# YutaAndJialiang_v17.net
KiCad netlist of a schematic drawn in EAGLE
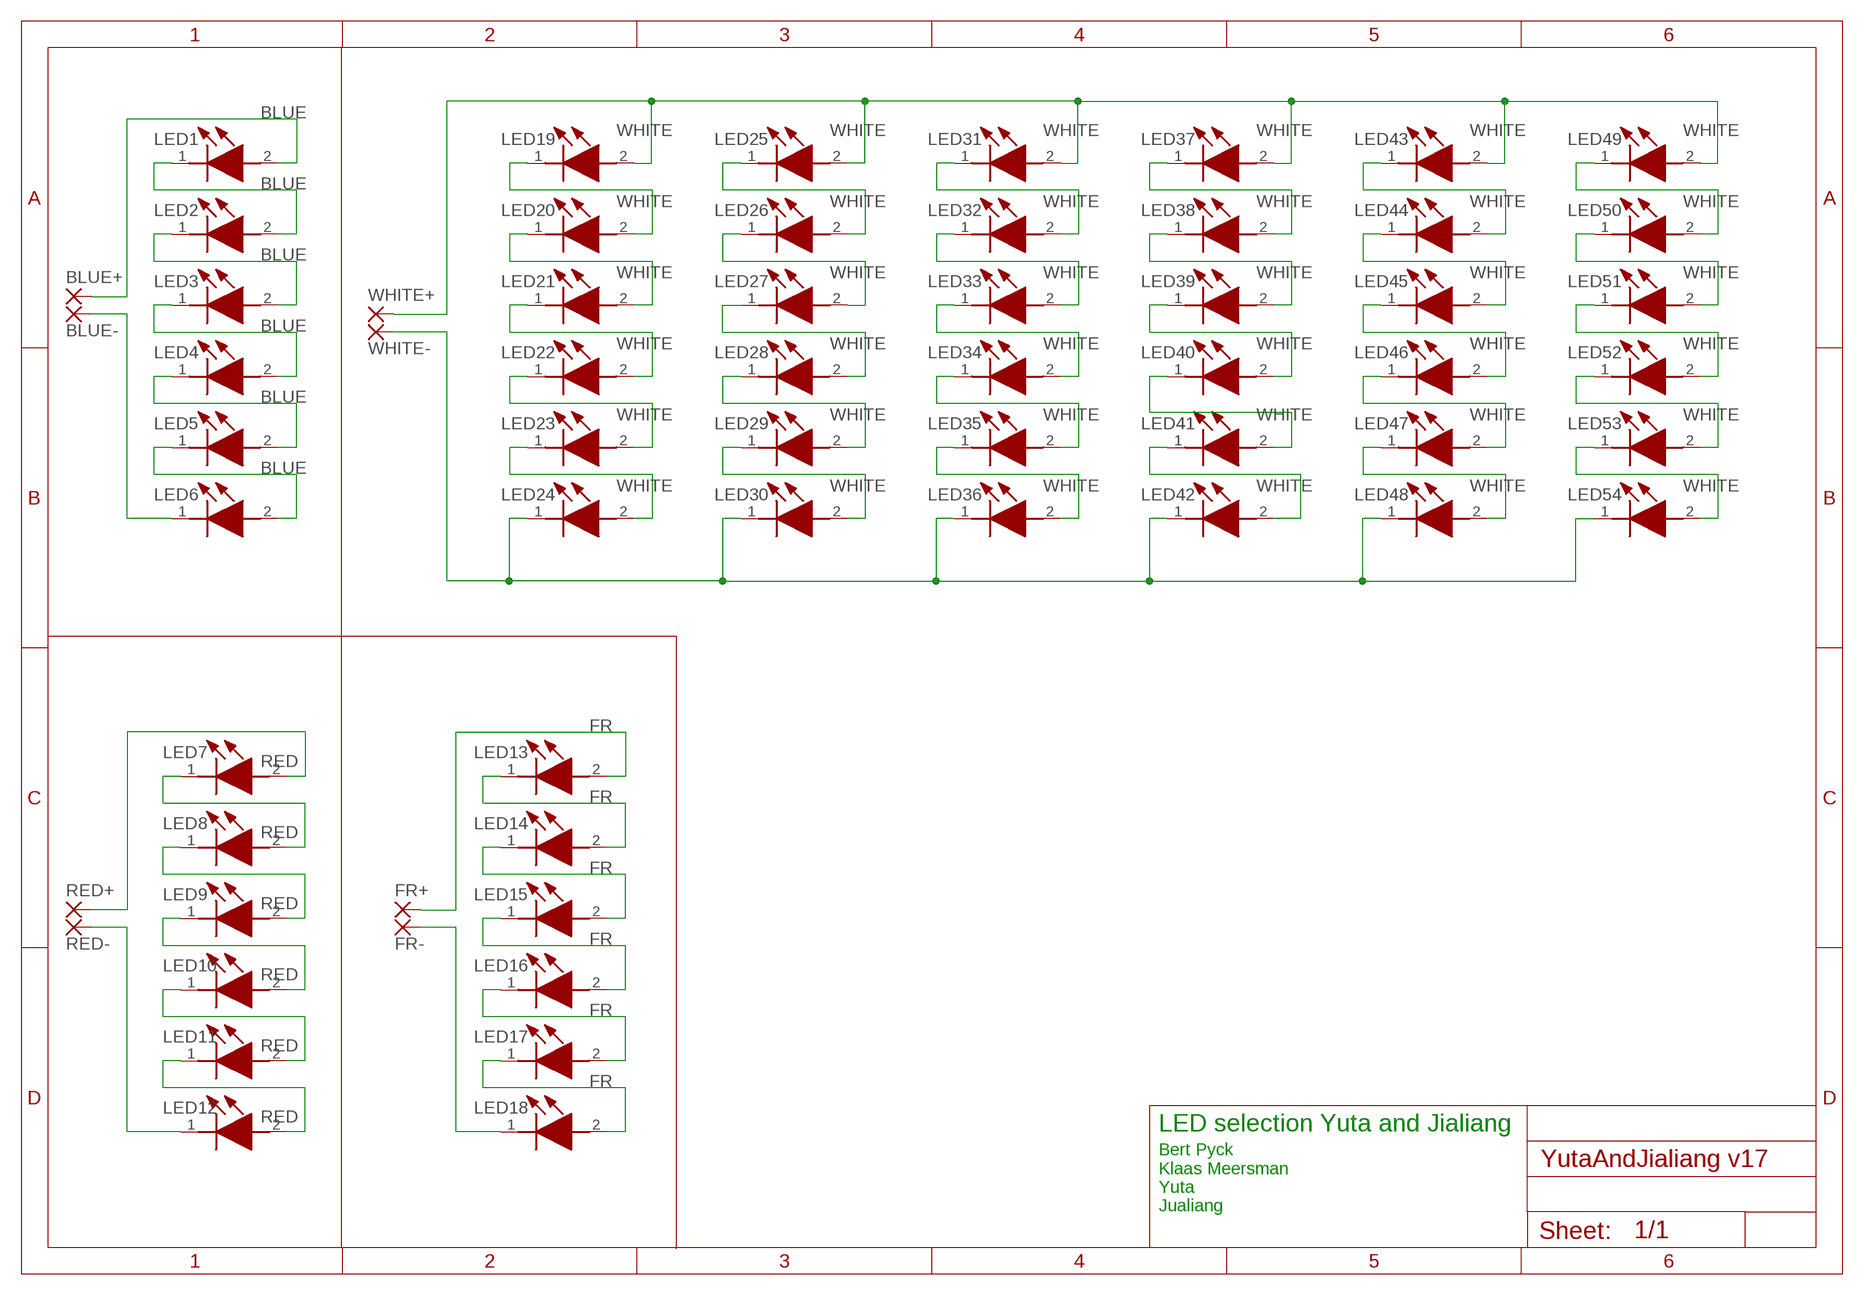
[diagram p0: schematic, sheet 1]

(export (version "E")
  (design (tool "Eeschema 10.0.6"))
  (components
    (comp (ref "BLUE+")
      (value "SOLDERPAD")
      (footprint "eagle-import:SOLDERPAD")
      (libsource (lib "eagle-import") (part "SOLDERPAD"))
    )
    (comp (ref "BLUE-")
      (value "SOLDERPAD")
      (footprint "eagle-import:SOLDERPAD")
      (libsource (lib "eagle-import") (part "SOLDERPAD"))
    )
    (comp (ref "FR+")
      (value "SOLDERPAD")
      (footprint "eagle-import:SOLDERPAD")
      (libsource (lib "eagle-import") (part "SOLDERPAD"))
    )
    (comp (ref "FR-")
      (value "SOLDERPAD")
      (footprint "eagle-import:SOLDERPAD")
      (libsource (lib "eagle-import") (part "SOLDERPAD"))
    )
    (comp (ref "LED1")
      (value "BLUE")
      (footprint "eagle-import:L1SP-PNK1002800000")
      (fields
        (field (name "MANUFACTURER_PART_NUMBER") "JE2835AFR-N-0001A0000-N0000001")
        (field (name "MOUSER_PART_NUMBER") "941-JE2835AFRN01AN")
      )
      (libsource (lib "eagle-import") (part "BLUE"))
    )
    (comp (ref "LED2")
      (value "BLUE")
      (footprint "eagle-import:L1SP-PNK1002800000")
      (fields
        (field (name "MANUFACTURER_PART_NUMBER") "JE2835AFR-N-0001A0000-N0000001")
        (field (name "MOUSER_PART_NUMBER") "941-JE2835AFRN01AN")
      )
      (libsource (lib "eagle-import") (part "BLUE"))
    )
    (comp (ref "LED3")
      (value "BLUE")
      (footprint "eagle-import:L1SP-PNK1002800000")
      (fields
        (field (name "MANUFACTURER_PART_NUMBER") "JE2835AFR-N-0001A0000-N0000001")
        (field (name "MOUSER_PART_NUMBER") "941-JE2835AFRN01AN")
      )
      (libsource (lib "eagle-import") (part "BLUE"))
    )
    (comp (ref "LED4")
      (value "BLUE")
      (footprint "eagle-import:L1SP-PNK1002800000")
      (fields
        (field (name "MANUFACTURER_PART_NUMBER") "JE2835AFR-N-0001A0000-N0000001")
        (field (name "MOUSER_PART_NUMBER") "941-JE2835AFRN01AN")
      )
      (libsource (lib "eagle-import") (part "BLUE"))
    )
    (comp (ref "LED5")
      (value "BLUE")
      (footprint "eagle-import:L1SP-PNK1002800000")
      (fields
        (field (name "MANUFACTURER_PART_NUMBER") "JE2835AFR-N-0001A0000-N0000001")
        (field (name "MOUSER_PART_NUMBER") "941-JE2835AFRN01AN")
      )
      (libsource (lib "eagle-import") (part "BLUE"))
    )
    (comp (ref "LED6")
      (value "BLUE")
      (footprint "eagle-import:L1SP-PNK1002800000")
      (fields
        (field (name "MANUFACTURER_PART_NUMBER") "JE2835AFR-N-0001A0000-N0000001")
        (field (name "MOUSER_PART_NUMBER") "941-JE2835AFRN01AN")
      )
      (libsource (lib "eagle-import") (part "BLUE"))
    )
    (comp (ref "LED7")
      (value "RED")
      (footprint "eagle-import:L1SP-PNK1002800000")
      (fields
        (field (name "MANUFACTURER_PART_NUMBER") "JE2835AFR-N-0001A0000-N0000001")
        (field (name "MOUSER_PART_NUMBER") "941-JE2835AFRN01AN")
      )
      (libsource (lib "eagle-import") (part "RED"))
    )
    (comp (ref "LED8")
      (value "RED")
      (footprint "eagle-import:L1SP-PNK1002800000")
      (fields
        (field (name "MANUFACTURER_PART_NUMBER") "JE2835AFR-N-0001A0000-N0000001")
        (field (name "MOUSER_PART_NUMBER") "941-JE2835AFRN01AN")
      )
      (libsource (lib "eagle-import") (part "RED"))
    )
    (comp (ref "LED9")
      (value "RED")
      (footprint "eagle-import:L1SP-PNK1002800000")
      (fields
        (field (name "MANUFACTURER_PART_NUMBER") "JE2835AFR-N-0001A0000-N0000001")
        (field (name "MOUSER_PART_NUMBER") "941-JE2835AFRN01AN")
      )
      (libsource (lib "eagle-import") (part "RED"))
    )
    (comp (ref "LED10")
      (value "RED")
      (footprint "eagle-import:L1SP-PNK1002800000")
      (fields
        (field (name "MANUFACTURER_PART_NUMBER") "JE2835AFR-N-0001A0000-N0000001")
        (field (name "MOUSER_PART_NUMBER") "941-JE2835AFRN01AN")
      )
      (libsource (lib "eagle-import") (part "RED"))
    )
    (comp (ref "LED11")
      (value "RED")
      (footprint "eagle-import:L1SP-PNK1002800000")
      (fields
        (field (name "MANUFACTURER_PART_NUMBER") "JE2835AFR-N-0001A0000-N0000001")
        (field (name "MOUSER_PART_NUMBER") "941-JE2835AFRN01AN")
      )
      (libsource (lib "eagle-import") (part "RED"))
    )
    (comp (ref "LED12")
      (value "RED")
      (footprint "eagle-import:L1SP-PNK1002800000")
      (fields
        (field (name "MANUFACTURER_PART_NUMBER") "JE2835AFR-N-0001A0000-N0000001")
        (field (name "MOUSER_PART_NUMBER") "941-JE2835AFRN01AN")
      )
      (libsource (lib "eagle-import") (part "RED"))
    )
    (comp (ref "LED13")
      (value "FR")
      (footprint "eagle-import:L1SP-PNK1002800000")
      (fields
        (field (name "MANUFACTURER_PART_NUMBER") "JE2835AFR-N-0001A0000-N0000001")
        (field (name "MOUSER_PART_NUMBER") "941-JE2835AFRN01AN")
      )
      (libsource (lib "eagle-import") (part "FR"))
    )
    (comp (ref "LED14")
      (value "FR")
      (footprint "eagle-import:L1SP-PNK1002800000")
      (fields
        (field (name "MANUFACTURER_PART_NUMBER") "JE2835AFR-N-0001A0000-N0000001")
        (field (name "MOUSER_PART_NUMBER") "941-JE2835AFRN01AN")
      )
      (libsource (lib "eagle-import") (part "FR"))
    )
    (comp (ref "LED15")
      (value "FR")
      (footprint "eagle-import:L1SP-PNK1002800000")
      (fields
        (field (name "MANUFACTURER_PART_NUMBER") "JE2835AFR-N-0001A0000-N0000001")
        (field (name "MOUSER_PART_NUMBER") "941-JE2835AFRN01AN")
      )
      (libsource (lib "eagle-import") (part "FR"))
    )
    (comp (ref "LED16")
      (value "FR")
      (footprint "eagle-import:L1SP-PNK1002800000")
      (fields
        (field (name "MANUFACTURER_PART_NUMBER") "JE2835AFR-N-0001A0000-N0000001")
        (field (name "MOUSER_PART_NUMBER") "941-JE2835AFRN01AN")
      )
      (libsource (lib "eagle-import") (part "FR"))
    )
    (comp (ref "LED17")
      (value "FR")
      (footprint "eagle-import:L1SP-PNK1002800000")
      (fields
        (field (name "MANUFACTURER_PART_NUMBER") "JE2835AFR-N-0001A0000-N0000001")
        (field (name "MOUSER_PART_NUMBER") "941-JE2835AFRN01AN")
      )
      (libsource (lib "eagle-import") (part "FR"))
    )
    (comp (ref "LED18")
      (value "FR")
      (footprint "eagle-import:L1SP-PNK1002800000")
      (fields
        (field (name "MANUFACTURER_PART_NUMBER") "JE2835AFR-N-0001A0000-N0000001")
        (field (name "MOUSER_PART_NUMBER") "941-JE2835AFRN01AN")
      )
      (libsource (lib "eagle-import") (part "FR"))
    )
    (comp (ref "LED19")
      (value "WHITE")
      (footprint "eagle-import:L1SP-PNK1002800000")
      (fields
        (field (name "MANUFACTURER_PART_NUMBER") "JE2835AFR-N-0001A0000-N0000001")
        (field (name "MOUSER_PART_NUMBER") "941-JE2835AFRN01AN")
      )
      (libsource (lib "eagle-import") (part "WHITE"))
    )
    (comp (ref "LED20")
      (value "WHITE")
      (footprint "eagle-import:L1SP-PNK1002800000")
      (fields
        (field (name "MANUFACTURER_PART_NUMBER") "JE2835AFR-N-0001A0000-N0000001")
        (field (name "MOUSER_PART_NUMBER") "941-JE2835AFRN01AN")
      )
      (libsource (lib "eagle-import") (part "WHITE"))
    )
    (comp (ref "LED21")
      (value "WHITE")
      (footprint "eagle-import:L1SP-PNK1002800000")
      (fields
        (field (name "MANUFACTURER_PART_NUMBER") "JE2835AFR-N-0001A0000-N0000001")
        (field (name "MOUSER_PART_NUMBER") "941-JE2835AFRN01AN")
      )
      (libsource (lib "eagle-import") (part "WHITE"))
    )
    (comp (ref "LED22")
      (value "WHITE")
      (footprint "eagle-import:L1SP-PNK1002800000")
      (fields
        (field (name "MANUFACTURER_PART_NUMBER") "JE2835AFR-N-0001A0000-N0000001")
        (field (name "MOUSER_PART_NUMBER") "941-JE2835AFRN01AN")
      )
      (libsource (lib "eagle-import") (part "WHITE"))
    )
    (comp (ref "LED23")
      (value "WHITE")
      (footprint "eagle-import:L1SP-PNK1002800000")
      (fields
        (field (name "MANUFACTURER_PART_NUMBER") "JE2835AFR-N-0001A0000-N0000001")
        (field (name "MOUSER_PART_NUMBER") "941-JE2835AFRN01AN")
      )
      (libsource (lib "eagle-import") (part "WHITE"))
    )
    (comp (ref "LED24")
      (value "WHITE")
      (footprint "eagle-import:L1SP-PNK1002800000")
      (fields
        (field (name "MANUFACTURER_PART_NUMBER") "JE2835AFR-N-0001A0000-N0000001")
        (field (name "MOUSER_PART_NUMBER") "941-JE2835AFRN01AN")
      )
      (libsource (lib "eagle-import") (part "WHITE"))
    )
    (comp (ref "LED25")
      (value "WHITE")
      (footprint "eagle-import:L1SP-PNK1002800000")
      (fields
        (field (name "MANUFACTURER_PART_NUMBER") "JE2835AFR-N-0001A0000-N0000001")
        (field (name "MOUSER_PART_NUMBER") "941-JE2835AFRN01AN")
      )
      (libsource (lib "eagle-import") (part "WHITE"))
    )
    (comp (ref "LED26")
      (value "WHITE")
      (footprint "eagle-import:L1SP-PNK1002800000")
      (fields
        (field (name "MANUFACTURER_PART_NUMBER") "JE2835AFR-N-0001A0000-N0000001")
        (field (name "MOUSER_PART_NUMBER") "941-JE2835AFRN01AN")
      )
      (libsource (lib "eagle-import") (part "WHITE"))
    )
    (comp (ref "LED27")
      (value "WHITE")
      (footprint "eagle-import:L1SP-PNK1002800000")
      (fields
        (field (name "MANUFACTURER_PART_NUMBER") "JE2835AFR-N-0001A0000-N0000001")
        (field (name "MOUSER_PART_NUMBER") "941-JE2835AFRN01AN")
      )
      (libsource (lib "eagle-import") (part "WHITE"))
    )
    (comp (ref "LED28")
      (value "WHITE")
      (footprint "eagle-import:L1SP-PNK1002800000")
      (fields
        (field (name "MANUFACTURER_PART_NUMBER") "JE2835AFR-N-0001A0000-N0000001")
        (field (name "MOUSER_PART_NUMBER") "941-JE2835AFRN01AN")
      )
      (libsource (lib "eagle-import") (part "WHITE"))
    )
    (comp (ref "LED29")
      (value "WHITE")
      (footprint "eagle-import:L1SP-PNK1002800000")
      (fields
        (field (name "MANUFACTURER_PART_NUMBER") "JE2835AFR-N-0001A0000-N0000001")
        (field (name "MOUSER_PART_NUMBER") "941-JE2835AFRN01AN")
      )
      (libsource (lib "eagle-import") (part "WHITE"))
    )
    (comp (ref "LED30")
      (value "WHITE")
      (footprint "eagle-import:L1SP-PNK1002800000")
      (fields
        (field (name "MANUFACTURER_PART_NUMBER") "JE2835AFR-N-0001A0000-N0000001")
        (field (name "MOUSER_PART_NUMBER") "941-JE2835AFRN01AN")
      )
      (libsource (lib "eagle-import") (part "WHITE"))
    )
    (comp (ref "LED31")
      (value "WHITE")
      (footprint "eagle-import:L1SP-PNK1002800000")
      (fields
        (field (name "MANUFACTURER_PART_NUMBER") "JE2835AFR-N-0001A0000-N0000001")
        (field (name "MOUSER_PART_NUMBER") "941-JE2835AFRN01AN")
      )
      (libsource (lib "eagle-import") (part "WHITE"))
    )
    (comp (ref "LED32")
      (value "WHITE")
      (footprint "eagle-import:L1SP-PNK1002800000")
      (fields
        (field (name "MANUFACTURER_PART_NUMBER") "JE2835AFR-N-0001A0000-N0000001")
        (field (name "MOUSER_PART_NUMBER") "941-JE2835AFRN01AN")
      )
      (libsource (lib "eagle-import") (part "WHITE"))
    )
    (comp (ref "LED33")
      (value "WHITE")
      (footprint "eagle-import:L1SP-PNK1002800000")
      (fields
        (field (name "MANUFACTURER_PART_NUMBER") "JE2835AFR-N-0001A0000-N0000001")
        (field (name "MOUSER_PART_NUMBER") "941-JE2835AFRN01AN")
      )
      (libsource (lib "eagle-import") (part "WHITE"))
    )
    (comp (ref "LED34")
      (value "WHITE")
      (footprint "eagle-import:L1SP-PNK1002800000")
      (fields
        (field (name "MANUFACTURER_PART_NUMBER") "JE2835AFR-N-0001A0000-N0000001")
        (field (name "MOUSER_PART_NUMBER") "941-JE2835AFRN01AN")
      )
      (libsource (lib "eagle-import") (part "WHITE"))
    )
    (comp (ref "LED35")
      (value "WHITE")
      (footprint "eagle-import:L1SP-PNK1002800000")
      (fields
        (field (name "MANUFACTURER_PART_NUMBER") "JE2835AFR-N-0001A0000-N0000001")
        (field (name "MOUSER_PART_NUMBER") "941-JE2835AFRN01AN")
      )
      (libsource (lib "eagle-import") (part "WHITE"))
    )
    (comp (ref "LED36")
      (value "WHITE")
      (footprint "eagle-import:L1SP-PNK1002800000")
      (fields
        (field (name "MANUFACTURER_PART_NUMBER") "JE2835AFR-N-0001A0000-N0000001")
        (field (name "MOUSER_PART_NUMBER") "941-JE2835AFRN01AN")
      )
      (libsource (lib "eagle-import") (part "WHITE"))
    )
    (comp (ref "LED37")
      (value "WHITE")
      (footprint "eagle-import:L1SP-PNK1002800000")
      (fields
        (field (name "MANUFACTURER_PART_NUMBER") "JE2835AFR-N-0001A0000-N0000001")
        (field (name "MOUSER_PART_NUMBER") "941-JE2835AFRN01AN")
      )
      (libsource (lib "eagle-import") (part "WHITE"))
    )
    (comp (ref "LED38")
      (value "WHITE")
      (footprint "eagle-import:L1SP-PNK1002800000")
      (fields
        (field (name "MANUFACTURER_PART_NUMBER") "JE2835AFR-N-0001A0000-N0000001")
        (field (name "MOUSER_PART_NUMBER") "941-JE2835AFRN01AN")
      )
      (libsource (lib "eagle-import") (part "WHITE"))
    )
    (comp (ref "LED39")
      (value "WHITE")
      (footprint "eagle-import:L1SP-PNK1002800000")
      (fields
        (field (name "MANUFACTURER_PART_NUMBER") "JE2835AFR-N-0001A0000-N0000001")
        (field (name "MOUSER_PART_NUMBER") "941-JE2835AFRN01AN")
      )
      (libsource (lib "eagle-import") (part "WHITE"))
    )
    (comp (ref "LED40")
      (value "WHITE")
      (footprint "eagle-import:L1SP-PNK1002800000")
      (fields
        (field (name "MANUFACTURER_PART_NUMBER") "JE2835AFR-N-0001A0000-N0000001")
        (field (name "MOUSER_PART_NUMBER") "941-JE2835AFRN01AN")
      )
      (libsource (lib "eagle-import") (part "WHITE"))
    )
    (comp (ref "LED41")
      (value "WHITE")
      (footprint "eagle-import:L1SP-PNK1002800000")
      (fields
        (field (name "MANUFACTURER_PART_NUMBER") "JE2835AFR-N-0001A0000-N0000001")
        (field (name "MOUSER_PART_NUMBER") "941-JE2835AFRN01AN")
      )
      (libsource (lib "eagle-import") (part "WHITE"))
    )
    (comp (ref "LED42")
      (value "WHITE")
      (footprint "eagle-import:L1SP-PNK1002800000")
      (fields
        (field (name "MANUFACTURER_PART_NUMBER") "JE2835AFR-N-0001A0000-N0000001")
        (field (name "MOUSER_PART_NUMBER") "941-JE2835AFRN01AN")
      )
      (libsource (lib "eagle-import") (part "WHITE"))
    )
    (comp (ref "LED43")
      (value "WHITE")
      (footprint "eagle-import:L1SP-PNK1002800000")
      (fields
        (field (name "MANUFACTURER_PART_NUMBER") "JE2835AFR-N-0001A0000-N0000001")
        (field (name "MOUSER_PART_NUMBER") "941-JE2835AFRN01AN")
      )
      (libsource (lib "eagle-import") (part "WHITE"))
    )
    (comp (ref "LED44")
      (value "WHITE")
      (footprint "eagle-import:L1SP-PNK1002800000")
      (fields
        (field (name "MANUFACTURER_PART_NUMBER") "JE2835AFR-N-0001A0000-N0000001")
        (field (name "MOUSER_PART_NUMBER") "941-JE2835AFRN01AN")
      )
      (libsource (lib "eagle-import") (part "WHITE"))
    )
    (comp (ref "LED45")
      (value "WHITE")
      (footprint "eagle-import:L1SP-PNK1002800000")
      (fields
        (field (name "MANUFACTURER_PART_NUMBER") "JE2835AFR-N-0001A0000-N0000001")
        (field (name "MOUSER_PART_NUMBER") "941-JE2835AFRN01AN")
      )
      (libsource (lib "eagle-import") (part "WHITE"))
    )
    (comp (ref "LED46")
      (value "WHITE")
      (footprint "eagle-import:L1SP-PNK1002800000")
      (fields
        (field (name "MANUFACTURER_PART_NUMBER") "JE2835AFR-N-0001A0000-N0000001")
        (field (name "MOUSER_PART_NUMBER") "941-JE2835AFRN01AN")
      )
      (libsource (lib "eagle-import") (part "WHITE"))
    )
    (comp (ref "LED47")
      (value "WHITE")
      (footprint "eagle-import:L1SP-PNK1002800000")
      (fields
        (field (name "MANUFACTURER_PART_NUMBER") "JE2835AFR-N-0001A0000-N0000001")
        (field (name "MOUSER_PART_NUMBER") "941-JE2835AFRN01AN")
      )
      (libsource (lib "eagle-import") (part "WHITE"))
    )
    (comp (ref "LED48")
      (value "WHITE")
      (footprint "eagle-import:L1SP-PNK1002800000")
      (fields
        (field (name "MANUFACTURER_PART_NUMBER") "JE2835AFR-N-0001A0000-N0000001")
        (field (name "MOUSER_PART_NUMBER") "941-JE2835AFRN01AN")
      )
      (libsource (lib "eagle-import") (part "WHITE"))
    )
    (comp (ref "LED49")
      (value "WHITE")
      (footprint "eagle-import:L1SP-PNK1002800000")
      (fields
        (field (name "MANUFACTURER_PART_NUMBER") "JE2835AFR-N-0001A0000-N0000001")
        (field (name "MOUSER_PART_NUMBER") "941-JE2835AFRN01AN")
      )
      (libsource (lib "eagle-import") (part "WHITE"))
    )
    (comp (ref "LED50")
      (value "WHITE")
      (footprint "eagle-import:L1SP-PNK1002800000")
      (fields
        (field (name "MANUFACTURER_PART_NUMBER") "JE2835AFR-N-0001A0000-N0000001")
        (field (name "MOUSER_PART_NUMBER") "941-JE2835AFRN01AN")
      )
      (libsource (lib "eagle-import") (part "WHITE"))
    )
    (comp (ref "LED51")
      (value "WHITE")
      (footprint "eagle-import:L1SP-PNK1002800000")
      (fields
        (field (name "MANUFACTURER_PART_NUMBER") "JE2835AFR-N-0001A0000-N0000001")
        (field (name "MOUSER_PART_NUMBER") "941-JE2835AFRN01AN")
      )
      (libsource (lib "eagle-import") (part "WHITE"))
    )
    (comp (ref "LED52")
      (value "WHITE")
      (footprint "eagle-import:L1SP-PNK1002800000")
      (fields
        (field (name "MANUFACTURER_PART_NUMBER") "JE2835AFR-N-0001A0000-N0000001")
        (field (name "MOUSER_PART_NUMBER") "941-JE2835AFRN01AN")
      )
      (libsource (lib "eagle-import") (part "WHITE"))
    )
    (comp (ref "LED53")
      (value "WHITE")
      (footprint "eagle-import:L1SP-PNK1002800000")
      (fields
        (field (name "MANUFACTURER_PART_NUMBER") "JE2835AFR-N-0001A0000-N0000001")
        (field (name "MOUSER_PART_NUMBER") "941-JE2835AFRN01AN")
      )
      (libsource (lib "eagle-import") (part "WHITE"))
    )
    (comp (ref "LED54")
      (value "WHITE")
      (footprint "eagle-import:L1SP-PNK1002800000")
      (fields
        (field (name "MANUFACTURER_PART_NUMBER") "JE2835AFR-N-0001A0000-N0000001")
        (field (name "MOUSER_PART_NUMBER") "941-JE2835AFRN01AN")
      )
      (libsource (lib "eagle-import") (part "WHITE"))
    )
    (comp (ref "RED+")
      (value "SOLDERPAD")
      (footprint "eagle-import:SOLDERPAD")
      (libsource (lib "eagle-import") (part "SOLDERPAD"))
    )
    (comp (ref "RED-")
      (value "SOLDERPAD")
      (footprint "eagle-import:SOLDERPAD")
      (libsource (lib "eagle-import") (part "SOLDERPAD"))
    )
    (comp (ref "WHITE+")
      (value "SOLDERPAD")
      (footprint "eagle-import:SOLDERPAD")
      (libsource (lib "eagle-import") (part "SOLDERPAD"))
    )
    (comp (ref "WHITE-")
      (value "SOLDERPAD")
      (footprint "eagle-import:SOLDERPAD")
      (libsource (lib "eagle-import") (part "SOLDERPAD"))
    )
  )
  (nets
    (net (code "1") (name "Net-(BLUE+-P)") (class "Default")
      (node (ref "BLUE+") (pin "1") (pinfunction "P_1") (pintype "passive"))
      (node (ref "LED1") (pin "2") (pinfunction "A_2") (pintype "bidirectional"))
    )
    (net (code "2") (name "Net-(BLUE--P)") (class "Default")
      (node (ref "BLUE-") (pin "1") (pinfunction "P_1") (pintype "passive"))
      (node (ref "LED6") (pin "1") (pinfunction "K_1") (pintype "bidirectional"))
    )
    (net (code "3") (name "Net-(FR+-P)") (class "Default")
      (node (ref "FR+") (pin "1") (pinfunction "P_1") (pintype "passive"))
      (node (ref "LED13") (pin "2") (pinfunction "A_2") (pintype "bidirectional"))
    )
    (net (code "4") (name "Net-(FR--P)") (class "Default")
      (node (ref "FR-") (pin "1") (pinfunction "P_1") (pintype "passive"))
      (node (ref "LED18") (pin "1") (pinfunction "K_1") (pintype "bidirectional"))
    )
    (net (code "5") (name "Net-(LED1-K)") (class "Default")
      (node (ref "LED1") (pin "1") (pinfunction "K_1") (pintype "bidirectional"))
      (node (ref "LED2") (pin "2") (pinfunction "A_2") (pintype "bidirectional"))
    )
    (net (code "6") (name "Net-(LED2-K)") (class "Default")
      (node (ref "LED2") (pin "1") (pinfunction "K_1") (pintype "bidirectional"))
      (node (ref "LED3") (pin "2") (pinfunction "A_2") (pintype "bidirectional"))
    )
    (net (code "7") (name "Net-(LED3-K)") (class "Default")
      (node (ref "LED3") (pin "1") (pinfunction "K_1") (pintype "bidirectional"))
      (node (ref "LED4") (pin "2") (pinfunction "A_2") (pintype "bidirectional"))
    )
    (net (code "8") (name "Net-(LED4-K)") (class "Default")
      (node (ref "LED4") (pin "1") (pinfunction "K_1") (pintype "bidirectional"))
      (node (ref "LED5") (pin "2") (pinfunction "A_2") (pintype "bidirectional"))
    )
    (net (code "9") (name "Net-(LED5-K)") (class "Default")
      (node (ref "LED5") (pin "1") (pinfunction "K_1") (pintype "bidirectional"))
      (node (ref "LED6") (pin "2") (pinfunction "A_2") (pintype "bidirectional"))
    )
    (net (code "10") (name "Net-(LED7-A)") (class "Default")
      (node (ref "LED7") (pin "2") (pinfunction "A_2") (pintype "bidirectional"))
      (node (ref "RED+") (pin "1") (pinfunction "P_1") (pintype "passive"))
    )
    (net (code "11") (name "Net-(LED7-K)") (class "Default")
      (node (ref "LED7") (pin "1") (pinfunction "K_1") (pintype "bidirectional"))
      (node (ref "LED8") (pin "2") (pinfunction "A_2") (pintype "bidirectional"))
    )
    (net (code "12") (name "Net-(LED8-K)") (class "Default")
      (node (ref "LED8") (pin "1") (pinfunction "K_1") (pintype "bidirectional"))
      (node (ref "LED9") (pin "2") (pinfunction "A_2") (pintype "bidirectional"))
    )
    (net (code "13") (name "Net-(LED10-A)") (class "Default")
      (node (ref "LED10") (pin "2") (pinfunction "A_2") (pintype "bidirectional"))
      (node (ref "LED9") (pin "1") (pinfunction "K_1") (pintype "bidirectional"))
    )
    (net (code "14") (name "Net-(LED10-K)") (class "Default")
      (node (ref "LED10") (pin "1") (pinfunction "K_1") (pintype "bidirectional"))
      (node (ref "LED11") (pin "2") (pinfunction "A_2") (pintype "bidirectional"))
    )
    (net (code "15") (name "Net-(LED11-K)") (class "Default")
      (node (ref "LED11") (pin "1") (pinfunction "K_1") (pintype "bidirectional"))
      (node (ref "LED12") (pin "2") (pinfunction "A_2") (pintype "bidirectional"))
    )
    (net (code "16") (name "Net-(LED12-K)") (class "Default")
      (node (ref "LED12") (pin "1") (pinfunction "K_1") (pintype "bidirectional"))
      (node (ref "RED-") (pin "1") (pinfunction "P_1") (pintype "passive"))
    )
    (net (code "17") (name "Net-(LED13-K)") (class "Default")
      (node (ref "LED13") (pin "1") (pinfunction "K_1") (pintype "bidirectional"))
      (node (ref "LED14") (pin "2") (pinfunction "A_2") (pintype "bidirectional"))
    )
    (net (code "18") (name "Net-(LED14-K)") (class "Default")
      (node (ref "LED14") (pin "1") (pinfunction "K_1") (pintype "bidirectional"))
      (node (ref "LED15") (pin "2") (pinfunction "A_2") (pintype "bidirectional"))
    )
    (net (code "19") (name "Net-(LED15-K)") (class "Default")
      (node (ref "LED15") (pin "1") (pinfunction "K_1") (pintype "bidirectional"))
      (node (ref "LED16") (pin "2") (pinfunction "A_2") (pintype "bidirectional"))
    )
    (net (code "20") (name "Net-(LED16-K)") (class "Default")
      (node (ref "LED16") (pin "1") (pinfunction "K_1") (pintype "bidirectional"))
      (node (ref "LED17") (pin "2") (pinfunction "A_2") (pintype "bidirectional"))
    )
    (net (code "21") (name "Net-(LED17-K)") (class "Default")
      (node (ref "LED17") (pin "1") (pinfunction "K_1") (pintype "bidirectional"))
      (node (ref "LED18") (pin "2") (pinfunction "A_2") (pintype "bidirectional"))
    )
    (net (code "22") (name "Net-(LED19-A)") (class "Default")
      (node (ref "LED19") (pin "2") (pinfunction "A_2") (pintype "bidirectional"))
      (node (ref "LED25") (pin "2") (pinfunction "A_2") (pintype "bidirectional"))
      (node (ref "LED31") (pin "2") (pinfunction "A_2") (pintype "bidirectional"))
      (node (ref "LED37") (pin "2") (pinfunction "A_2") (pintype "bidirectional"))
      (node (ref "LED43") (pin "2") (pinfunction "A_2") (pintype "bidirectional"))
      (node (ref "LED49") (pin "2") (pinfunction "A_2") (pintype "bidirectional"))
      (node (ref "WHITE+") (pin "1") (pinfunction "P_1") (pintype "passive"))
    )
    (net (code "23") (name "Net-(LED19-K)") (class "Default")
      (node (ref "LED19") (pin "1") (pinfunction "K_1") (pintype "bidirectional"))
      (node (ref "LED20") (pin "2") (pinfunction "A_2") (pintype "bidirectional"))
    )
    (net (code "24") (name "Net-(LED20-K)") (class "Default")
      (node (ref "LED20") (pin "1") (pinfunction "K_1") (pintype "bidirectional"))
      (node (ref "LED21") (pin "2") (pinfunction "A_2") (pintype "bidirectional"))
    )
    (net (code "25") (name "Net-(LED21-K)") (class "Default")
      (node (ref "LED21") (pin "1") (pinfunction "K_1") (pintype "bidirectional"))
      (node (ref "LED22") (pin "2") (pinfunction "A_2") (pintype "bidirectional"))
    )
    (net (code "26") (name "Net-(LED22-K)") (class "Default")
      (node (ref "LED22") (pin "1") (pinfunction "K_1") (pintype "bidirectional"))
      (node (ref "LED23") (pin "2") (pinfunction "A_2") (pintype "bidirectional"))
    )
    (net (code "27") (name "Net-(LED23-K)") (class "Default")
      (node (ref "LED23") (pin "1") (pinfunction "K_1") (pintype "bidirectional"))
      (node (ref "LED24") (pin "2") (pinfunction "A_2") (pintype "bidirectional"))
    )
    (net (code "28") (name "Net-(LED24-K)") (class "Default")
      (node (ref "LED24") (pin "1") (pinfunction "K_1") (pintype "bidirectional"))
      (node (ref "LED30") (pin "1") (pinfunction "K_1") (pintype "bidirectional"))
      (node (ref "LED36") (pin "1") (pinfunction "K_1") (pintype "bidirectional"))
      (node (ref "LED42") (pin "1") (pinfunction "K_1") (pintype "bidirectional"))
      (node (ref "LED48") (pin "1") (pinfunction "K_1") (pintype "bidirectional"))
      (node (ref "LED54") (pin "1") (pinfunction "K_1") (pintype "bidirectional"))
      (node (ref "WHITE-") (pin "1") (pinfunction "P_1") (pintype "passive"))
    )
    (net (code "29") (name "Net-(LED25-K)") (class "Default")
      (node (ref "LED25") (pin "1") (pinfunction "K_1") (pintype "bidirectional"))
      (node (ref "LED26") (pin "2") (pinfunction "A_2") (pintype "bidirectional"))
    )
    (net (code "30") (name "Net-(LED26-K)") (class "Default")
      (node (ref "LED26") (pin "1") (pinfunction "K_1") (pintype "bidirectional"))
      (node (ref "LED27") (pin "2") (pinfunction "A_2") (pintype "bidirectional"))
    )
    (net (code "31") (name "Net-(LED27-K)") (class "Default")
      (node (ref "LED27") (pin "1") (pinfunction "K_1") (pintype "bidirectional"))
      (node (ref "LED28") (pin "2") (pinfunction "A_2") (pintype "bidirectional"))
    )
    (net (code "32") (name "Net-(LED28-K)") (class "Default")
      (node (ref "LED28") (pin "1") (pinfunction "K_1") (pintype "bidirectional"))
      (node (ref "LED29") (pin "2") (pinfunction "A_2") (pintype "bidirectional"))
    )
    (net (code "33") (name "Net-(LED29-K)") (class "Default")
      (node (ref "LED29") (pin "1") (pinfunction "K_1") (pintype "bidirectional"))
      (node (ref "LED30") (pin "2") (pinfunction "A_2") (pintype "bidirectional"))
    )
    (net (code "34") (name "Net-(LED31-K)") (class "Default")
      (node (ref "LED31") (pin "1") (pinfunction "K_1") (pintype "bidirectional"))
      (node (ref "LED32") (pin "2") (pinfunction "A_2") (pintype "bidirectional"))
    )
    (net (code "35") (name "Net-(LED32-K)") (class "Default")
      (node (ref "LED32") (pin "1") (pinfunction "K_1") (pintype "bidirectional"))
      (node (ref "LED33") (pin "2") (pinfunction "A_2") (pintype "bidirectional"))
    )
    (net (code "36") (name "Net-(LED33-K)") (class "Default")
      (node (ref "LED33") (pin "1") (pinfunction "K_1") (pintype "bidirectional"))
      (node (ref "LED34") (pin "2") (pinfunction "A_2") (pintype "bidirectional"))
    )
    (net (code "37") (name "Net-(LED34-K)") (class "Default")
      (node (ref "LED34") (pin "1") (pinfunction "K_1") (pintype "bidirectional"))
      (node (ref "LED35") (pin "2") (pinfunction "A_2") (pintype "bidirectional"))
    )
    (net (code "38") (name "Net-(LED35-K)") (class "Default")
      (node (ref "LED35") (pin "1") (pinfunction "K_1") (pintype "bidirectional"))
      (node (ref "LED36") (pin "2") (pinfunction "A_2") (pintype "bidirectional"))
    )
    (net (code "39") (name "Net-(LED37-K)") (class "Default")
      (node (ref "LED37") (pin "1") (pinfunction "K_1") (pintype "bidirectional"))
      (node (ref "LED38") (pin "2") (pinfunction "A_2") (pintype "bidirectional"))
    )
    (net (code "40") (name "Net-(LED38-K)") (class "Default")
      (node (ref "LED38") (pin "1") (pinfunction "K_1") (pintype "bidirectional"))
      (node (ref "LED39") (pin "2") (pinfunction "A_2") (pintype "bidirectional"))
    )
    (net (code "41") (name "Net-(LED39-K)") (class "Default")
      (node (ref "LED39") (pin "1") (pinfunction "K_1") (pintype "bidirectional"))
      (node (ref "LED40") (pin "2") (pinfunction "A_2") (pintype "bidirectional"))
    )
    (net (code "42") (name "Net-(LED40-K)") (class "Default")
      (node (ref "LED40") (pin "1") (pinfunction "K_1") (pintype "bidirectional"))
      (node (ref "LED41") (pin "2") (pinfunction "A_2") (pintype "bidirectional"))
    )
    (net (code "43") (name "Net-(LED41-K)") (class "Default")
      (node (ref "LED41") (pin "1") (pinfunction "K_1") (pintype "bidirectional"))
      (node (ref "LED42") (pin "2") (pinfunction "A_2") (pintype "bidirectional"))
    )
    (net (code "44") (name "Net-(LED43-K)") (class "Default")
      (node (ref "LED43") (pin "1") (pinfunction "K_1") (pintype "bidirectional"))
      (node (ref "LED44") (pin "2") (pinfunction "A_2") (pintype "bidirectional"))
    )
    (net (code "45") (name "Net-(LED44-K)") (class "Default")
      (node (ref "LED44") (pin "1") (pinfunction "K_1") (pintype "bidirectional"))
      (node (ref "LED45") (pin "2") (pinfunction "A_2") (pintype "bidirectional"))
    )
    (net (code "46") (name "Net-(LED45-K)") (class "Default")
      (node (ref "LED45") (pin "1") (pinfunction "K_1") (pintype "bidirectional"))
      (node (ref "LED46") (pin "2") (pinfunction "A_2") (pintype "bidirectional"))
    )
    (net (code "47") (name "Net-(LED46-K)") (class "Default")
      (node (ref "LED46") (pin "1") (pinfunction "K_1") (pintype "bidirectional"))
      (node (ref "LED47") (pin "2") (pinfunction "A_2") (pintype "bidirectional"))
    )
    (net (code "48") (name "Net-(LED47-K)") (class "Default")
      (node (ref "LED47") (pin "1") (pinfunction "K_1") (pintype "bidirectional"))
      (node (ref "LED48") (pin "2") (pinfunction "A_2") (pintype "bidirectional"))
    )
    (net (code "49") (name "Net-(LED49-K)") (class "Default")
      (node (ref "LED49") (pin "1") (pinfunction "K_1") (pintype "bidirectional"))
      (node (ref "LED50") (pin "2") (pinfunction "A_2") (pintype "bidirectional"))
    )
    (net (code "50") (name "Net-(LED50-K)") (class "Default")
      (node (ref "LED50") (pin "1") (pinfunction "K_1") (pintype "bidirectional"))
      (node (ref "LED51") (pin "2") (pinfunction "A_2") (pintype "bidirectional"))
    )
    (net (code "51") (name "Net-(LED51-K)") (class "Default")
      (node (ref "LED51") (pin "1") (pinfunction "K_1") (pintype "bidirectional"))
      (node (ref "LED52") (pin "2") (pinfunction "A_2") (pintype "bidirectional"))
    )
    (net (code "52") (name "Net-(LED52-K)") (class "Default")
      (node (ref "LED52") (pin "1") (pinfunction "K_1") (pintype "bidirectional"))
      (node (ref "LED53") (pin "2") (pinfunction "A_2") (pintype "bidirectional"))
    )
    (net (code "53") (name "Net-(LED53-K)") (class "Default")
      (node (ref "LED53") (pin "1") (pinfunction "K_1") (pintype "bidirectional"))
      (node (ref "LED54") (pin "2") (pinfunction "A_2") (pintype "bidirectional"))
    )
  )
)
